# USB_PC.net
KiCad netlist of a schematic drawn in EAGLE
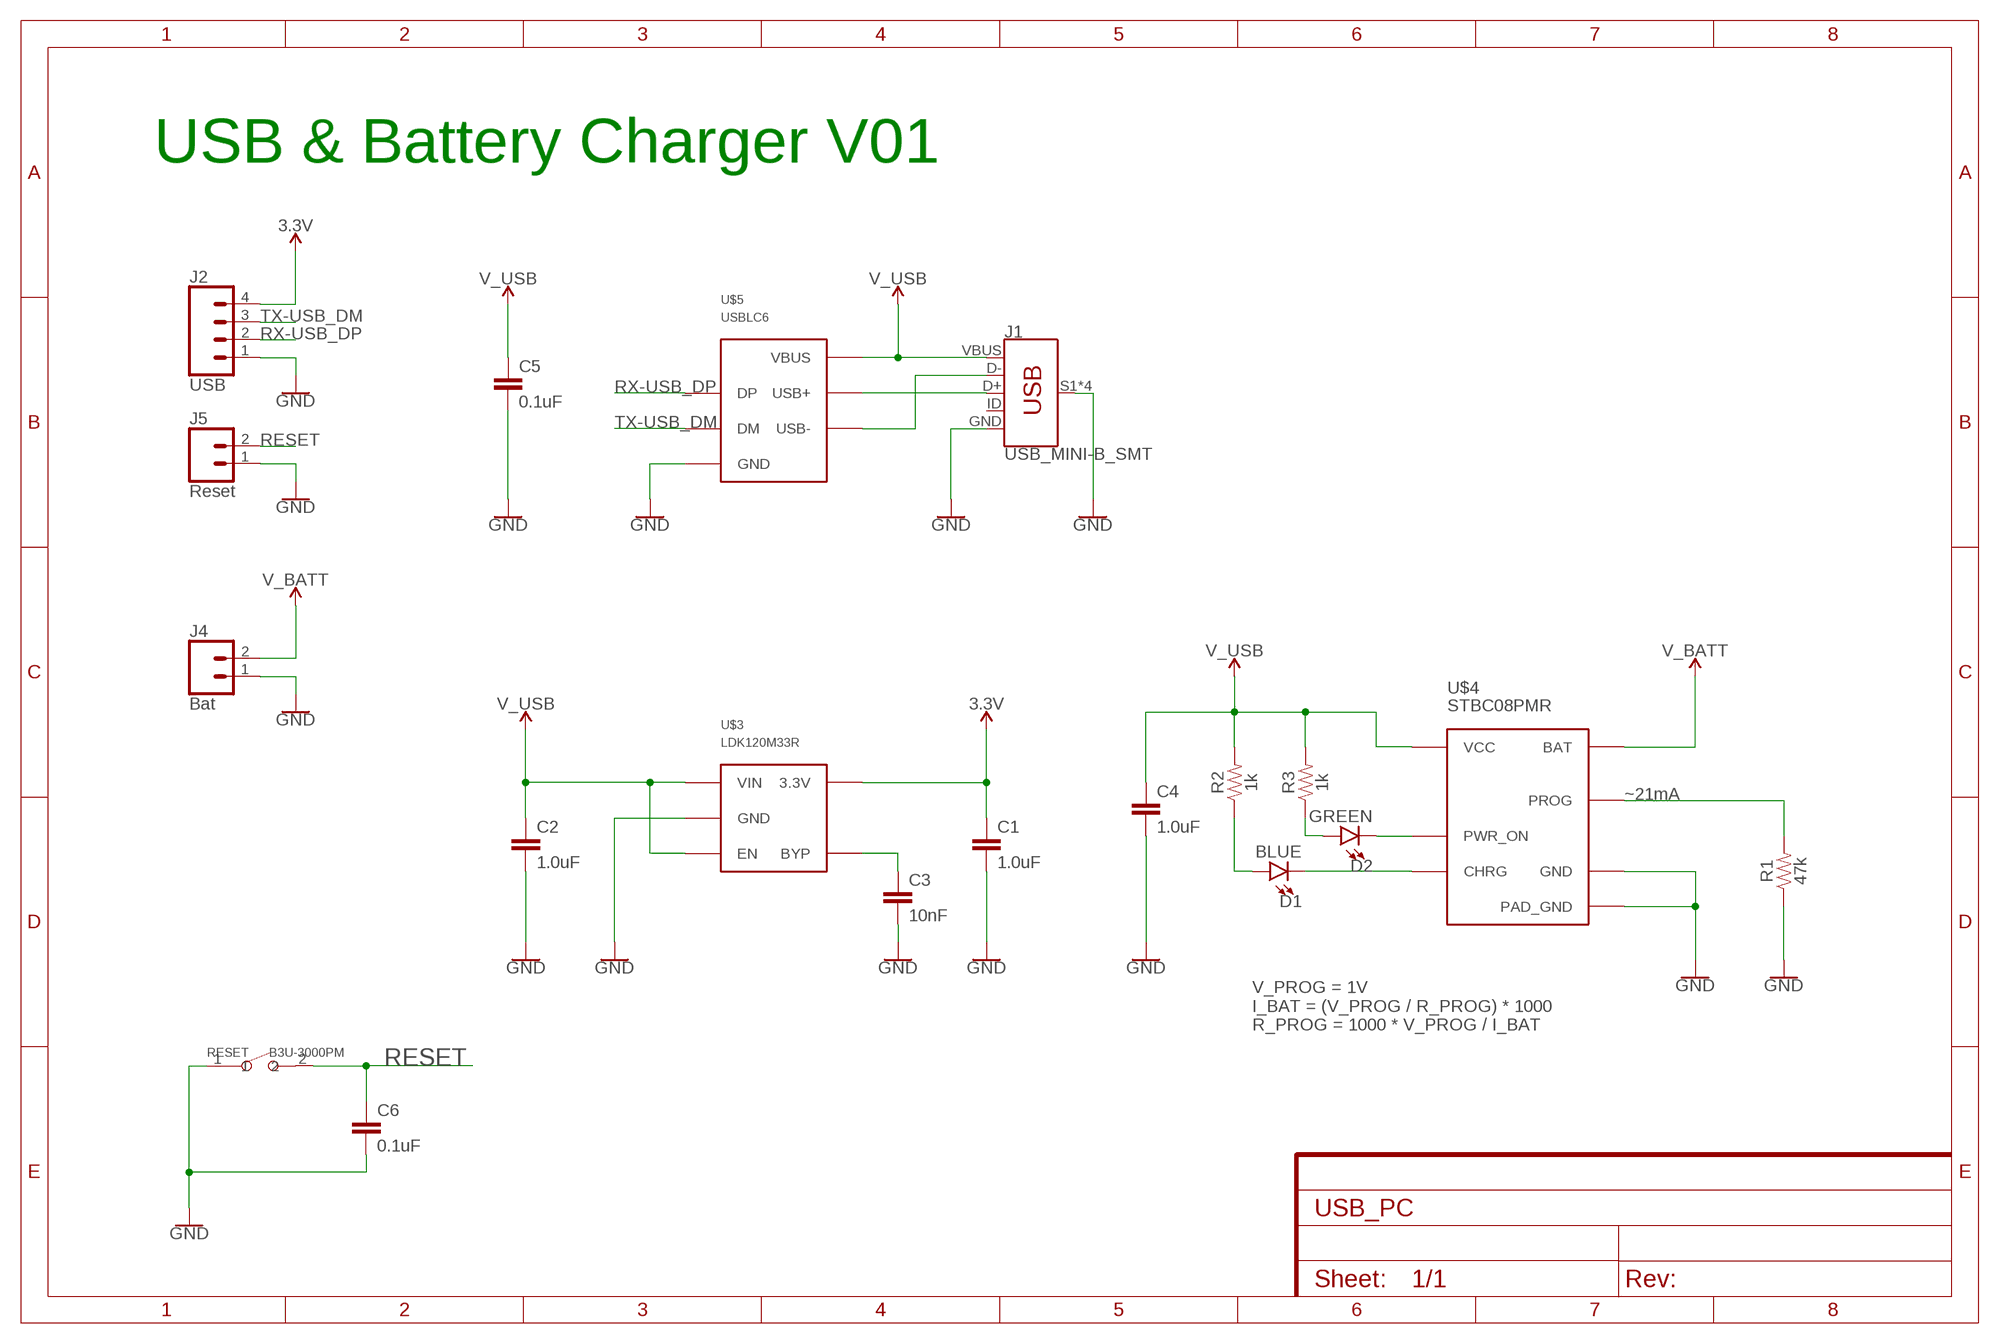
[diagram p0: schematic, sheet 1]

(export (version "E")
  (design (tool "Eeschema 10.0.6"))
  (components
    (comp (ref "C1")
      (value "1.0uF")
      (footprint "eagle-import:0603")
      (libsource (lib "eagle-import") (part "1.0UF-0603-16V-10%"))
    )
    (comp (ref "C2")
      (value "1.0uF")
      (footprint "eagle-import:0603")
      (libsource (lib "eagle-import") (part "1.0UF-0603-16V-10%"))
    )
    (comp (ref "C3")
      (value "10nF")
      (footprint "eagle-import:0603")
      (libsource (lib "eagle-import") (part "10NF-0603-50V-10%"))
    )
    (comp (ref "C4")
      (value "1.0uF")
      (footprint "eagle-import:0603")
      (libsource (lib "eagle-import") (part "1.0UF-0603-16V-10%"))
    )
    (comp (ref "C5")
      (value "0.1uF")
      (footprint "eagle-import:0603")
      (libsource (lib "eagle-import") (part "0.1UF-0603-25V-5%"))
    )
    (comp (ref "C6")
      (value "0.1uF")
      (footprint "eagle-import:0603")
      (libsource (lib "eagle-import") (part "0.1UF-0603-25V-5%"))
    )
    (comp (ref "D1")
      (value "BLUE")
      (footprint "eagle-import:LED-0603")
      (libsource (lib "eagle-import") (part "LED-BLUE0603"))
    )
    (comp (ref "D2")
      (value "GREEN")
      (footprint "eagle-import:LED-0603")
      (libsource (lib "eagle-import") (part "LED-GREEN0603"))
    )
    (comp (ref "J1")
      (value "USB_MINI-B_SMT")
      (footprint "eagle-import:USB-MINIB")
      (libsource (lib "eagle-import") (part "USB_MINI-B_SMT"))
    )
    (comp (ref "J2")
      (value "USB")
      (footprint "eagle-import:1X04")
      (libsource (lib "eagle-import") (part "CONN_04"))
    )
    (comp (ref "J4")
      (value "Bat")
      (footprint "eagle-import:JST-2-PTH")
      (libsource (lib "eagle-import") (part "CONN_02JST-PTH-2"))
    )
    (comp (ref "J5")
      (value "Reset")
      (footprint "eagle-import:1X02")
      (libsource (lib "eagle-import") (part "CONN_02"))
    )
    (comp (ref "R1")
      (value "47k")
      (footprint "eagle-import:0603")
      (libsource (lib "eagle-import") (part "47KOHM-0603-1/10W-1%"))
    )
    (comp (ref "R2")
      (value "1k")
      (footprint "eagle-import:0603")
      (libsource (lib "eagle-import") (part "1KOHM-0603-1/10W-1%"))
    )
    (comp (ref "R3")
      (value "1k")
      (footprint "eagle-import:0603")
      (libsource (lib "eagle-import") (part "1KOHM-0603-1/10W-1%"))
    )
    (comp (ref "RESET")
      (value "B3U-3000PM")
      (footprint "eagle-import:SW2-2.6-3.0X2.5X1.2+0.4MM")
      (fields (field (name "MPN") "B3U-1000P-2P-SMD"))
      (libsource (lib "eagle-import") (part "SMD-BUTTON(2P-3.0X2.5X1.2+0.4MM)-B3U-1000P-2P-SMD"))
    )
    (comp (ref "U$3")
      (value "LDK120M33R")
      (footprint "eagle-import:SOT23-5")
      (libsource (lib "eagle-import") (part "LDK120M33R"))
    )
    (comp (ref "U$4")
      (value "STBC08PMR")
      (footprint "eagle-import:6-DFN(3X3)")
      (libsource (lib "eagle-import") (part "STBC08PMR"))
    )
    (comp (ref "U$5")
      (value "USBLC6")
      (footprint "eagle-import:SOT23-6L")
      (libsource (lib "eagle-import") (part "USBLC6-2SC6"))
    )
  )
  (nets
    (net (code "1") (name "/RESET") (class "Default")
      (node (ref "C6") (pin "1") (pinfunction "1_1") (pintype "passive"))
      (node (ref "J5") (pin "2") (pinfunction "2_2") (pintype "passive"))
      (node (ref "RESET") (pin "2") (pinfunction "2_2") (pintype "bidirectional"))
    )
    (net (code "2") (name "/RX-USB_DP") (class "Default")
      (node (ref "J2") (pin "2") (pinfunction "2_2") (pintype "passive"))
      (node (ref "U$5") (pin "D+IN$1") (pinfunction "DP_D+IN$1") (pintype "bidirectional"))
    )
    (net (code "3") (name "/TX-USB_DM") (class "Default")
      (node (ref "J2") (pin "3") (pinfunction "3_3") (pintype "passive"))
      (node (ref "U$5") (pin "D-IN$3") (pinfunction "DM_D-IN$3") (pintype "bidirectional"))
    )
    (net (code "4") (name "3.3V") (class "Default")
      (node (ref "C1") (pin "1") (pinfunction "1_1") (pintype "passive"))
      (node (ref "J2") (pin "4") (pinfunction "4_4") (pintype "passive"))
      (node (ref "U$3") (pin "3V3&5") (pinfunction "3.3V_3V3&5") (pintype "bidirectional"))
    )
    (net (code "5") (name "GND") (class "Default")
      (node (ref "C1") (pin "2") (pinfunction "2_2") (pintype "passive"))
      (node (ref "C2") (pin "2") (pinfunction "2_2") (pintype "passive"))
      (node (ref "C3") (pin "2") (pinfunction "2_2") (pintype "passive"))
      (node (ref "C4") (pin "2") (pinfunction "2_2") (pintype "passive"))
      (node (ref "C5") (pin "2") (pinfunction "2_2") (pintype "passive"))
      (node (ref "C6") (pin "2") (pinfunction "2_2") (pintype "passive"))
      (node (ref "J1") (pin "GND") (pinfunction "GND_GND") (pintype "power_in"))
      (node (ref "J1") (pin "S1") (pinfunction "SHIELD_S1") (pintype "bidirectional"))
      (node (ref "J1") (pin "S2") (pinfunction "SHIELD_S2") (pintype "bidirectional"))
      (node (ref "J1") (pin "S3") (pinfunction "SHIELD_S3") (pintype "bidirectional"))
      (node (ref "J1") (pin "S4") (pinfunction "SHIELD_S4") (pintype "bidirectional"))
      (node (ref "J2") (pin "1") (pinfunction "1_1") (pintype "passive"))
      (node (ref "J4") (pin "1") (pinfunction "1_1") (pintype "passive"))
      (node (ref "J5") (pin "1") (pinfunction "1_1") (pintype "passive"))
      (node (ref "R1") (pin "1") (pinfunction "1_1") (pintype "passive"))
      (node (ref "RESET") (pin "1") (pinfunction "1_1") (pintype "bidirectional"))
      (node (ref "U$3") (pin "GND$2") (pinfunction "GND_GND$2") (pintype "bidirectional"))
      (node (ref "U$4") (pin "GND$4") (pinfunction "GND_GND$4") (pintype "bidirectional"))
      (node (ref "U$4") (pin "PAD_GND$7") (pinfunction "PAD_GND_PAD_GND$7") (pintype "bidirectional"))
      (node (ref "U$5") (pin "GND$2") (pinfunction "GND_GND$2") (pintype "bidirectional"))
    )
    (net (code "6") (name "Net-(D1-PadA)") (class "Default")
      (node (ref "D1") (pin "A") (pinfunction "A_A") (pintype "passive"))
      (node (ref "R2") (pin "1") (pinfunction "1_1") (pintype "passive"))
    )
    (net (code "7") (name "Net-(D2-PadA)") (class "Default")
      (node (ref "D2") (pin "A") (pinfunction "A_A") (pintype "passive"))
      (node (ref "R3") (pin "1") (pinfunction "1_1") (pintype "passive"))
    )
    (net (code "8") (name "Net-(U$3-BYP)") (class "Default")
      (node (ref "C3") (pin "1") (pinfunction "1_1") (pintype "passive"))
      (node (ref "U$3") (pin "BYP$4") (pinfunction "BYP_BYP$4") (pintype "bidirectional"))
    )
    (net (code "9") (name "Net-(U$4-CHRG)") (class "Default")
      (node (ref "D1") (pin "C") (pinfunction "C_C") (pintype "passive"))
      (node (ref "U$4") (pin "CHRG$3") (pinfunction "CHRG_CHRG$3") (pintype "bidirectional"))
    )
    (net (code "10") (name "Net-(U$4-PROG)") (class "Default")
      (node (ref "R1") (pin "2") (pinfunction "2_2") (pintype "passive"))
      (node (ref "U$4") (pin "PROG$5") (pinfunction "PROG_PROG$5") (pintype "bidirectional"))
    )
    (net (code "11") (name "Net-(U$4-PWR_ON)") (class "Default")
      (node (ref "D2") (pin "C") (pinfunction "C_C") (pintype "passive"))
      (node (ref "U$4") (pin "ON$2") (pinfunction "PWR_ON_ON$2") (pintype "bidirectional"))
    )
    (net (code "12") (name "Net-(U$5-USB+)") (class "Default")
      (node (ref "J1") (pin "D+") (pinfunction "D+_D+") (pintype "bidirectional"))
      (node (ref "U$5") (pin "D+OUT$1$6") (pinfunction "USB+_D+OUT$1$6") (pintype "bidirectional"))
    )
    (net (code "13") (name "Net-(U$5-USB-)") (class "Default")
      (node (ref "J1") (pin "D-") (pinfunction "D-_D-") (pintype "bidirectional"))
      (node (ref "U$5") (pin "D-OUT$1$4") (pinfunction "USB-_D-OUT$1$4") (pintype "bidirectional"))
    )
    (net (code "14") (name "V_BATT") (class "Default")
      (node (ref "J4") (pin "2") (pinfunction "2_2") (pintype "passive"))
      (node (ref "U$4") (pin "BAT$1") (pinfunction "BAT_BAT$1") (pintype "bidirectional"))
    )
    (net (code "15") (name "V_USB") (class "Default")
      (node (ref "C2") (pin "1") (pinfunction "1_1") (pintype "passive"))
      (node (ref "C4") (pin "1") (pinfunction "1_1") (pintype "passive"))
      (node (ref "C5") (pin "1") (pinfunction "1_1") (pintype "passive"))
      (node (ref "J1") (pin "VBUS") (pinfunction "VBUS_VBUS") (pintype "power_in"))
      (node (ref "R2") (pin "2") (pinfunction "2_2") (pintype "passive"))
      (node (ref "R3") (pin "2") (pinfunction "2_2") (pintype "passive"))
      (node (ref "U$3") (pin "EN$3") (pinfunction "EN_EN$3") (pintype "bidirectional"))
      (node (ref "U$3") (pin "VIN$1") (pinfunction "VIN_VIN$1") (pintype "bidirectional"))
      (node (ref "U$4") (pin "VCC$6") (pinfunction "VCC_VCC$6") (pintype "bidirectional"))
      (node (ref "U$5") (pin "VUSB$5") (pinfunction "VBUS_VUSB$5") (pintype "bidirectional"))
    )
    (net (code "16") (name "unconnected-(J1-PadID)") (class "Default")
      (node (ref "J1") (pin "ID") (pinfunction "ID_ID") (pintype "bidirectional"))
    )
  )
)
